# BreakResistor.net
KiCad netlist of a schematic drawn in Altium Designer
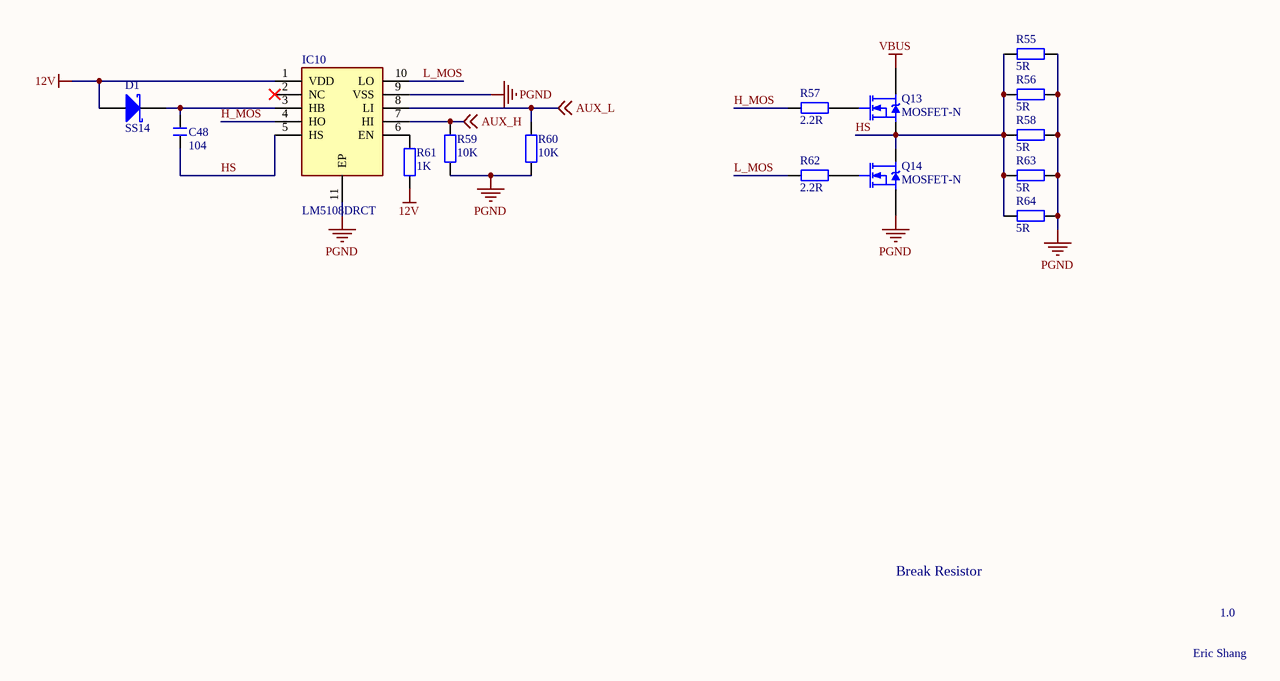
[diagram p0: BreakResistor.SchDoc]

(export (version "E")
  (design (tool "Eeschema 10.0.6"))
  (components
    (comp (ref "C48")
      (value "104")
      (footprint "C 0603_L")
      (description "贴片电容")
      (libsource (lib "0.1 - 电阻-电容-电感") (part "C"))
    )
    (comp (ref "D1")
      (value "SS14")
      (footprint "SMA")
      (description "肖特基二极管")
      (libsource (lib "0.2 -  二极管-整流桥") (part "SS14"))
    )
    (comp (ref "IC10")
      (value "LM5108DRCT")
      (footprint "SkylakeADPcbLib:SON50P300X300X100-11N-D")
      (description "Integrated Circuit")
      (fields (field (name "MOUSER PART NUMBER") "595-LM5108DRCT"))
      (libsource (lib "SkylakeADSchLib") (part "LM5108DRCT"))
    )
    (comp (ref "Q13")
      (value "MOSFET-N")
      (footprint "TO263-3B")
      (description "N-Channel MOSFET")
      (fields (field (name "PUBLISHER") "Altium Limited"))
      (libsource (lib "0.5 - 场效应管-可控硅") (part "MOSFET-N"))
    )
    (comp (ref "Q14")
      (value "MOSFET-N")
      (footprint "TO263-3B")
      (description "N-Channel MOSFET")
      (fields (field (name "PUBLISHER") "Altium Limited"))
      (libsource (lib "0.5 - 场效应管-可控硅") (part "MOSFET-N"))
    )
    (comp (ref "R55")
      (value "5R")
      (footprint "RX10-18*15*5")
      (description "5W无感水泥电阻")
      (fields (field (name "版权归属") "封装库来自淘宝 ID：黄晶宝石"))
      (libsource (lib "0.1 - 电阻-电容-电感") (part "R_MPR"))
    )
    (comp (ref "R56")
      (value "5R")
      (footprint "RX10-18*15*5")
      (description "5W无感水泥电阻")
      (fields (field (name "版权归属") "封装库来自淘宝 ID：黄晶宝石"))
      (libsource (lib "0.1 - 电阻-电容-电感") (part "R_MPR"))
    )
    (comp (ref "R57")
      (value "2.2R")
      (footprint "R 0603_L")
      (description "贴片电阻")
      (fields (field (name "版权归属") "来自淘宝 ID：黄晶宝石"))
      (libsource (lib "0.1 - 电阻-电容-电感") (part "R"))
    )
    (comp (ref "R58")
      (value "5R")
      (footprint "RX10-18*15*5")
      (description "5W无感水泥电阻")
      (fields (field (name "版权归属") "封装库来自淘宝 ID：黄晶宝石"))
      (libsource (lib "0.1 - 电阻-电容-电感") (part "R_MPR"))
    )
    (comp (ref "R59")
      (value "10K")
      (footprint "R 0603_L")
      (description "贴片电阻")
      (fields (field (name "版权归属") "来自淘宝 ID：黄晶宝石"))
      (libsource (lib "0.1 - 电阻-电容-电感") (part "R"))
    )
    (comp (ref "R60")
      (value "10K")
      (footprint "R 0603_L")
      (description "贴片电阻")
      (fields (field (name "版权归属") "来自淘宝 ID：黄晶宝石"))
      (libsource (lib "0.1 - 电阻-电容-电感") (part "R"))
    )
    (comp (ref "R61")
      (value "1K")
      (footprint "R 0603_L")
      (description "贴片电阻")
      (fields (field (name "版权归属") "来自淘宝 ID：黄晶宝石"))
      (libsource (lib "0.1 - 电阻-电容-电感") (part "R"))
    )
    (comp (ref "R62")
      (value "2.2R")
      (footprint "R 0603_L")
      (description "贴片电阻")
      (fields (field (name "版权归属") "来自淘宝 ID：黄晶宝石"))
      (libsource (lib "0.1 - 电阻-电容-电感") (part "R"))
    )
    (comp (ref "R63")
      (value "5R")
      (footprint "RX10-18*15*5")
      (description "5W无感水泥电阻")
      (fields (field (name "版权归属") "封装库来自淘宝 ID：黄晶宝石"))
      (libsource (lib "0.1 - 电阻-电容-电感") (part "R_MPR"))
    )
    (comp (ref "R64")
      (value "5R")
      (footprint "RX10-18*15*5")
      (description "5W无感水泥电阻")
      (fields (field (name "版权归属") "封装库来自淘宝 ID：黄晶宝石"))
      (libsource (lib "0.1 - 电阻-电容-电感") (part "R_MPR"))
    )
  )
  (nets
    (net (code "1") (name "/HS") (class "Default")
      (node (ref "C48") (pin "1") (pinfunction "1_1") (pintype "passive"))
      (node (ref "IC10") (pin "5") (pinfunction "HS_5") (pintype "passive"))
      (node (ref "Q13") (pin "3") (pinfunction "S_3") (pintype "passive"))
      (node (ref "Q14") (pin "2") (pinfunction "D_2") (pintype "passive"))
      (node (ref "R55") (pin "1") (pinfunction "1_1") (pintype "passive"))
      (node (ref "R56") (pin "1") (pinfunction "1_1") (pintype "passive"))
      (node (ref "R58") (pin "1") (pinfunction "1_1") (pintype "passive"))
      (node (ref "R63") (pin "1") (pinfunction "1_1") (pintype "passive"))
      (node (ref "R64") (pin "1") (pinfunction "1_1") (pintype "passive"))
    )
    (net (code "2") (name "/H_MOS") (class "Default")
      (node (ref "IC10") (pin "4") (pinfunction "HO_4") (pintype "passive"))
      (node (ref "R57") (pin "1") (pinfunction "1_1") (pintype "passive"))
    )
    (net (code "3") (name "/L_MOS") (class "Default")
      (node (ref "IC10") (pin "10") (pinfunction "LO_10") (pintype "passive"))
      (node (ref "R62") (pin "1") (pinfunction "1_1") (pintype "passive"))
    )
    (net (code "4") (name "12V") (class "Default")
      (node (ref "D1") (pin "1") (pinfunction "A_1") (pintype "passive"))
      (node (ref "IC10") (pin "1") (pinfunction "VDD_1") (pintype "passive"))
      (node (ref "R61") (pin "2") (pinfunction "2_2") (pintype "passive"))
    )
    (net (code "5") (name "AUX_H") (class "Default")
      (node (ref "IC10") (pin "7") (pinfunction "HI_7") (pintype "passive"))
      (node (ref "R59") (pin "1") (pinfunction "1_1") (pintype "passive"))
    )
    (net (code "6") (name "AUX_L") (class "Default")
      (node (ref "IC10") (pin "8") (pinfunction "LI_8") (pintype "passive"))
      (node (ref "R60") (pin "1") (pinfunction "1_1") (pintype "passive"))
    )
    (net (code "7") (name "Net-(D1-K)") (class "Default")
      (node (ref "C48") (pin "2") (pinfunction "2_2") (pintype "passive"))
      (node (ref "D1") (pin "2") (pinfunction "K_2") (pintype "passive"))
      (node (ref "IC10") (pin "3") (pinfunction "HB_3") (pintype "passive"))
    )
    (net (code "8") (name "Net-(IC10-EN)") (class "Default")
      (node (ref "IC10") (pin "6") (pinfunction "EN_6") (pintype "passive"))
      (node (ref "R61") (pin "1") (pinfunction "1_1") (pintype "passive"))
    )
    (net (code "9") (name "Net-(Q13-G)") (class "Default")
      (node (ref "Q13") (pin "1") (pinfunction "G_1") (pintype "passive"))
      (node (ref "R57") (pin "2") (pinfunction "2_2") (pintype "passive"))
    )
    (net (code "10") (name "Net-(Q14-G)") (class "Default")
      (node (ref "Q14") (pin "1") (pinfunction "G_1") (pintype "passive"))
      (node (ref "R62") (pin "2") (pinfunction "2_2") (pintype "passive"))
    )
    (net (code "11") (name "PGND") (class "Default")
      (node (ref "IC10") (pin "11") (pinfunction "EP_11") (pintype "passive"))
      (node (ref "IC10") (pin "9") (pinfunction "VSS_9") (pintype "passive"))
      (node (ref "Q14") (pin "3") (pinfunction "S_3") (pintype "passive"))
      (node (ref "R55") (pin "2") (pinfunction "2_2") (pintype "passive"))
      (node (ref "R56") (pin "2") (pinfunction "2_2") (pintype "passive"))
      (node (ref "R58") (pin "2") (pinfunction "2_2") (pintype "passive"))
      (node (ref "R59") (pin "2") (pinfunction "2_2") (pintype "passive"))
      (node (ref "R60") (pin "2") (pinfunction "2_2") (pintype "passive"))
      (node (ref "R63") (pin "2") (pinfunction "2_2") (pintype "passive"))
      (node (ref "R64") (pin "2") (pinfunction "2_2") (pintype "passive"))
    )
    (net (code "12") (name "VBUS") (class "Default")
      (node (ref "Q13") (pin "2") (pinfunction "D_2") (pintype "passive"))
    )
    (net (code "13") (name "unconnected-(IC10-NC-Pad2)") (class "Default")
      (node (ref "IC10") (pin "2") (pinfunction "NC_2") (pintype "passive+no_connect"))
    )
  )
)
